# Motor_Driver.net
KiCad netlist of a schematic drawn in Altium Designer
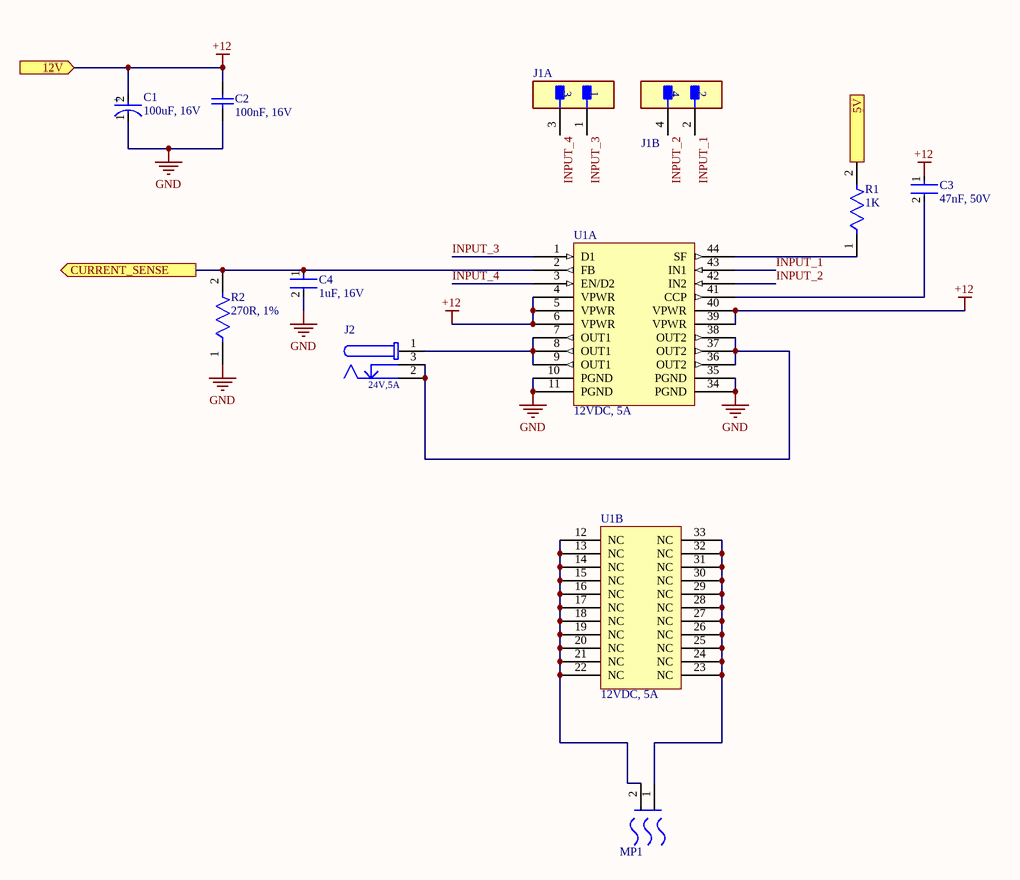
[diagram p0: Motor Driver.SchDoc]

(export (version "E")
  (design (tool "Eeschema 10.0.6"))
  (components
    (comp (ref "C1")
      (value "100uF, 16V")
      (footprint "FP-TAJF-MFG")
      (description "CAP TANT 100UF 20% 16V 2312")
      (fields (field (name "VOLTAGE") "16V") (field (name "TOLERANCE") "20%"))
      (libsource (lib "Altium Content Vault") (part "203bc49f2ac43e59fd269a8c329ed05"))
    )
    (comp (ref "C2")
      (value "100nF, 16V")
      (footprint "CAPC3216X180X55LL20T25")
      (description "Chip Capacitor, 100 nF, +/- 5%, 25 V, -55 to 125 degC, 1206 (3216 Metric), RoHS, Tape and Reel")
      (fields (field (name "MANUFACTURER") "Murata"))
      (libsource (lib "Altium Content Vault") (part "CAP-NP-2"))
    )
    (comp (ref "C3")
      (value "47nF, 50V")
      (footprint "FP-0805-L_2_01_0_2-W_1_25-IPC_C")
      (description "General Purpose Ceramic Capacitor, 0805, 47nF, 10%, X7R, 0.15, 50V")
      (fields (field (name "VOLTAGE") "50V") (field (name "TOLERANCE") "10%"))
      (libsource (lib "Altium Content Vault") (part "02cd4be3c70576c341d710602a673aa"))
    )
    (comp (ref "C4")
      (value "1uF, 16V")
      (footprint "FP-GCM219-0_15-MFG")
      (description "Ceramic Capacitor for Automotive 1uF  ±10% 16VDC X7R 0805 Paper T/R")
      (fields (field (name "TOLERANCE") "10%") (field (name "VOLTAGE") "16V"))
      (libsource (lib "Altium Content Vault") (part "11868f565c42a9108669ba33697ecf6"))
    )
    (comp (ref "J1")
      (value "5-146256-2")
      (footprint "FP-5-146256-2-MFG")
      (description "CONN HEADER VERT 4POS 2.54MM")
      (libsource (lib "Altium Content Vault") (part "1621473add15499e993d6bbd36d0f06"))
    )
    (comp (ref "J2")
      (value "24V,5A")
      (footprint "694106301002")
      (description "DC Power Jack Connector WR-DC, Male, Right Angled, THT, 5 A, 24 V")
      (fields
        (field (name "MANUFACTURER") "Wurth Elektronik")
        (field (name "PART NUMBER") "694106301002")
        (field (name "PUBLISHER") "WurthElektronik")
      )
      (libsource (lib "Altium Content Vault") (part "WE-JACK-2CD3-RN"))
    )
    (comp (ref "MP1")
      (value "R2A-CT4-38E")
      (footprint "FP-R2A-CT4-38E-MFG")
      (description "HEATSINK FOR TO-247")
      (libsource (lib "Altium Content Vault") (part "bada692059eb3cb02183618df46ea18"))
    )
    (comp (ref "R1")
      (value "1K")
      (footprint "FP-RC0805-0_6-MFG")
      (description "RES SMD 1K OHM 5% 1/8W 0805")
      (fields (field (name "TOLERANCE") "5%"))
      (libsource (lib "Altium Content Vault") (part "1029c3af85768c4190bb7ad29bc67b5"))
    )
    (comp (ref "R2")
      (value "270R, 1%")
      (footprint "FP-CR0805-IPC_B")
      (description "Thick Film Chip Resistors 0805 270Ω 0.125W 1% 100ppm/°C")
      (fields (field (name "TOLERANCE") "1%"))
      (libsource (lib "Altium Content Vault") (part "1029c3af85768c4190bb7ad29bc67b5"))
    )
    (comp (ref "U1")
      (value "12VDC, 5A")
      (footprint "SOP65P1420X340_HS-45N")
      (description "- Motor Driver CMOS Parallel 44-HSOP")
      (libsource (lib "Schlib1") (part "MC33931VWR2"))
    )
  )
  (nets
    (net (code "1") (name "+12") (class "Default")
      (node (ref "C1") (pin "2") (pinfunction "A_2") (pintype "passive"))
      (node (ref "C2") (pin "2") (pinfunction "2_2") (pintype "passive"))
      (node (ref "C3") (pin "1") (pinfunction "1_1") (pintype "passive"))
      (node (ref "U1") (pin "39") (pinfunction "VPWR_39") (pintype "power_in"))
      (node (ref "U1") (pin "4") (pinfunction "VPWR_4") (pintype "power_in"))
      (node (ref "U1") (pin "40") (pinfunction "VPWR_40") (pintype "power_in"))
      (node (ref "U1") (pin "5") (pinfunction "VPWR_5") (pintype "power_in"))
      (node (ref "U1") (pin "6") (pinfunction "VPWR_6") (pintype "power_in"))
    )
    (net (code "2") (name "/5V") (class "Default")
      (node (ref "R1") (pin "2") (pinfunction "2_2") (pintype "passive"))
    )
    (net (code "3") (name "/CURRENT_SENSE") (class "Default")
      (node (ref "C4") (pin "1") (pinfunction "1_1") (pintype "passive"))
      (node (ref "R2") (pin "2") (pinfunction "2_2") (pintype "passive"))
      (node (ref "U1") (pin "2") (pinfunction "FB_2") (pintype "output"))
    )
    (net (code "4") (name "/INPUT_1") (class "Default")
      (node (ref "J1") (pin "2") (pinfunction "2_2") (pintype "passive"))
      (node (ref "U1") (pin "43") (pinfunction "IN1_43") (pintype "input"))
    )
    (net (code "5") (name "/INPUT_2") (class "Default")
      (node (ref "J1") (pin "4") (pinfunction "4_4") (pintype "passive"))
      (node (ref "U1") (pin "42") (pinfunction "IN2_42") (pintype "input"))
    )
    (net (code "6") (name "/INPUT_3") (class "Default")
      (node (ref "J1") (pin "1") (pinfunction "1_1") (pintype "passive"))
      (node (ref "U1") (pin "1") (pinfunction "D1_1") (pintype "input"))
    )
    (net (code "7") (name "/INPUT_4") (class "Default")
      (node (ref "J1") (pin "3") (pinfunction "3_3") (pintype "passive"))
      (node (ref "U1") (pin "3") (pinfunction "EN/D2_3") (pintype "input"))
    )
    (net (code "8") (name "GND") (class "Default")
      (node (ref "C1") (pin "1") (pinfunction "C_1") (pintype "passive"))
      (node (ref "C2") (pin "1") (pinfunction "1_1") (pintype "passive"))
      (node (ref "C4") (pin "2") (pinfunction "2_2") (pintype "passive"))
      (node (ref "R2") (pin "1") (pinfunction "1_1") (pintype "passive"))
      (node (ref "U1") (pin "10") (pinfunction "PGND_10") (pintype "power_in"))
      (node (ref "U1") (pin "11") (pinfunction "PGND_11") (pintype "power_in"))
      (node (ref "U1") (pin "34") (pinfunction "PGND_34") (pintype "power_in"))
      (node (ref "U1") (pin "35") (pinfunction "PGND_35") (pintype "power_in"))
    )
    (net (code "9") (name "Net-(J2-Pad1)") (class "Default")
      (node (ref "J2") (pin "1") (pinfunction "1_1") (pintype "passive"))
      (node (ref "U1") (pin "7") (pinfunction "OUT1_7") (pintype "output"))
      (node (ref "U1") (pin "8") (pinfunction "OUT1_8") (pintype "output"))
      (node (ref "U1") (pin "9") (pinfunction "OUT1_9") (pintype "output"))
    )
    (net (code "10") (name "Net-(J2-Pad2)") (class "Default")
      (node (ref "J2") (pin "2") (pinfunction "2_2") (pintype "passive"))
      (node (ref "J2") (pin "3") (pinfunction "3_3") (pintype "passive"))
      (node (ref "U1") (pin "36") (pinfunction "OUT2_36") (pintype "output"))
      (node (ref "U1") (pin "37") (pinfunction "OUT2_37") (pintype "output"))
      (node (ref "U1") (pin "38") (pinfunction "OUT2_38") (pintype "output"))
    )
    (net (code "11") (name "Net-(MP1-Pad1)") (class "Default")
      (node (ref "MP1") (pin "1") (pinfunction "1_1") (pintype "passive"))
      (node (ref "U1") (pin "23") (pinfunction "NC_23") (pintype "passive"))
      (node (ref "U1") (pin "24") (pinfunction "NC_24") (pintype "passive"))
      (node (ref "U1") (pin "25") (pinfunction "NC_25") (pintype "passive"))
      (node (ref "U1") (pin "26") (pinfunction "NC_26") (pintype "passive"))
      (node (ref "U1") (pin "27") (pinfunction "NC_27") (pintype "passive"))
      (node (ref "U1") (pin "28") (pinfunction "NC_28") (pintype "passive"))
      (node (ref "U1") (pin "29") (pinfunction "NC_29") (pintype "passive"))
      (node (ref "U1") (pin "30") (pinfunction "NC_30") (pintype "passive"))
      (node (ref "U1") (pin "31") (pinfunction "NC_31") (pintype "passive"))
      (node (ref "U1") (pin "32") (pinfunction "NC_32") (pintype "passive"))
      (node (ref "U1") (pin "33") (pinfunction "NC_33") (pintype "passive"))
    )
    (net (code "12") (name "Net-(MP1-Pad2)") (class "Default")
      (node (ref "MP1") (pin "2") (pinfunction "2_2") (pintype "passive"))
      (node (ref "U1") (pin "12") (pinfunction "NC_12") (pintype "passive"))
      (node (ref "U1") (pin "13") (pinfunction "NC_13") (pintype "passive"))
      (node (ref "U1") (pin "14") (pinfunction "NC_14") (pintype "passive"))
      (node (ref "U1") (pin "15") (pinfunction "NC_15") (pintype "passive"))
      (node (ref "U1") (pin "16") (pinfunction "NC_16") (pintype "passive"))
      (node (ref "U1") (pin "17") (pinfunction "NC_17") (pintype "passive"))
      (node (ref "U1") (pin "18") (pinfunction "NC_18") (pintype "passive"))
      (node (ref "U1") (pin "19") (pinfunction "NC_19") (pintype "passive"))
      (node (ref "U1") (pin "20") (pinfunction "NC_20") (pintype "passive"))
      (node (ref "U1") (pin "21") (pinfunction "NC_21") (pintype "passive"))
      (node (ref "U1") (pin "22") (pinfunction "NC_22") (pintype "passive"))
    )
    (net (code "13") (name "Net-(U1A-CCP)") (class "Default")
      (node (ref "C3") (pin "2") (pinfunction "2_2") (pintype "passive"))
      (node (ref "U1") (pin "41") (pinfunction "CCP_41") (pintype "output"))
    )
    (net (code "14") (name "Net-(U1A-SF)") (class "Default")
      (node (ref "R1") (pin "1") (pinfunction "1_1") (pintype "passive"))
      (node (ref "U1") (pin "44") (pinfunction "SF_44") (pintype "output"))
    )
  )
)
